# MocKhoaTraiTim.net
KiCad netlist of a schematic drawn in Altium Designer
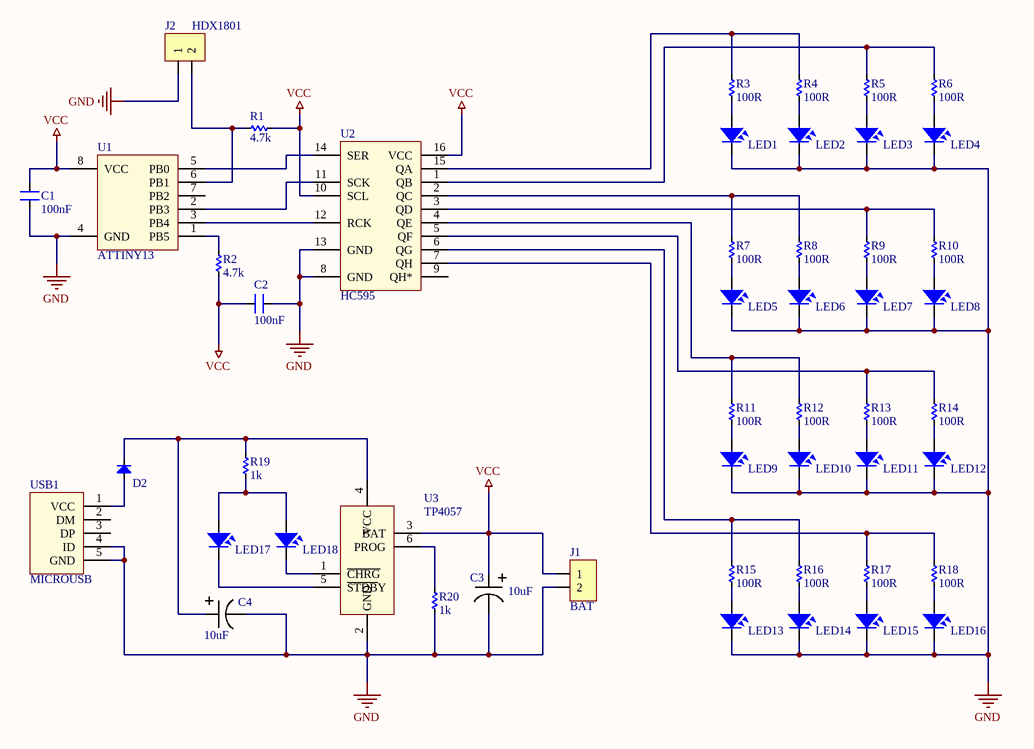
[diagram p0: MocKhoaTraiTim.SchDoc]

(export (version "E")
  (design (tool "Eeschema 10.0.6"))
  (components
    (comp (ref "C1") (value "100nF") (footprint "CN-SMD-0805") (libsource (lib "LIBRARY") (part "CN")))
    (comp (ref "C2") (value "100nF") (footprint "CN-SMD-0805") (libsource (lib "LIBRARY") (part "CN")))
    (comp (ref "C3") (value "10uF") (footprint "CAP1411") (libsource (lib "User") (part "CAP-TANTALUM")))
    (comp (ref "C4") (value "10uF") (footprint "CAP1411") (libsource (lib "") (part "CAP-TANTALUM_1")))
    (comp (ref "D2")
      (value "Diode SMD")
      (footprint "DIO-SMD-123")
      (description "Default Diode")
      (fields (field (name "PUBLISHER") "Altium Limited"))
      (libsource (lib "LIBRARY") (part "Diode SMD"))
    )
    (comp (ref "J1")
      (value "BAT")
      (footprint "JP2-D1T")
      (description "WR-PHD 2.54 mm Angled Socket Header")
      (fields
        (field (name "MANUFACTURER") "Würth Elektronik eiSos GmbH")
        (field (name "PARTNO") "613002143121")
        (field (name "CREATED BY") "Karrer Zheng")
      )
      (libsource (lib "LIBRARY") (part "JP2"))
    )
    (comp (ref "J2")
      (value "HDX1801")
      (footprint "JP2-D1T")
      (description "WR-PHD 2.54 mm Angled Socket Header")
      (fields
        (field (name "MANUFACTURER") "Würth Elektronik eiSos GmbH")
        (field (name "PARTNO") "613002143121")
        (field (name "CREATED BY") "Karrer Zheng")
      )
      (libsource (lib "") (part "JP2_1"))
    )
    (comp (ref "LED1")
      (value "LED")
      (footprint "LED-1206-Yellow")
      (libsource (lib "LIBRARY") (part "LED SMD"))
    )
    (comp (ref "LED2")
      (value "LED")
      (footprint "LED-1206-Yellow")
      (libsource (lib "LIBRARY") (part "LED SMD"))
    )
    (comp (ref "LED3")
      (value "LED")
      (footprint "LED-1206-Yellow")
      (libsource (lib "LIBRARY") (part "LED SMD"))
    )
    (comp (ref "LED4")
      (value "LED")
      (footprint "LED-1206-Yellow")
      (libsource (lib "LIBRARY") (part "LED SMD"))
    )
    (comp (ref "LED5")
      (value "LED")
      (footprint "LED-1206-Yellow")
      (libsource (lib "LIBRARY") (part "LED SMD"))
    )
    (comp (ref "LED6")
      (value "LED")
      (footprint "LED-1206-Yellow")
      (libsource (lib "LIBRARY") (part "LED SMD"))
    )
    (comp (ref "LED7")
      (value "LED")
      (footprint "LED-1206-Yellow")
      (libsource (lib "LIBRARY") (part "LED SMD"))
    )
    (comp (ref "LED8")
      (value "LED")
      (footprint "LED-1206-Yellow")
      (libsource (lib "LIBRARY") (part "LED SMD"))
    )
    (comp (ref "LED9")
      (value "LED")
      (footprint "LED-1206-Yellow")
      (libsource (lib "LIBRARY") (part "LED SMD"))
    )
    (comp (ref "LED10")
      (value "LED")
      (footprint "LED-1206-Yellow")
      (libsource (lib "LIBRARY") (part "LED SMD"))
    )
    (comp (ref "LED11")
      (value "LED")
      (footprint "LED-1206-Yellow")
      (libsource (lib "LIBRARY") (part "LED SMD"))
    )
    (comp (ref "LED12")
      (value "LED")
      (footprint "LED-1206-Yellow")
      (libsource (lib "LIBRARY") (part "LED SMD"))
    )
    (comp (ref "LED13")
      (value "LED")
      (footprint "LED-1206-Yellow")
      (libsource (lib "LIBRARY") (part "LED SMD"))
    )
    (comp (ref "LED14")
      (value "LED")
      (footprint "LED-1206-Yellow")
      (libsource (lib "LIBRARY") (part "LED SMD"))
    )
    (comp (ref "LED15")
      (value "LED")
      (footprint "LED-1206-Yellow")
      (libsource (lib "LIBRARY") (part "LED SMD"))
    )
    (comp (ref "LED16")
      (value "LED")
      (footprint "LED-1206-Yellow")
      (libsource (lib "LIBRARY") (part "LED SMD"))
    )
    (comp (ref "LED17")
      (value "LED")
      (footprint "LED-0805-Yellow")
      (libsource (lib "LIBRARY") (part "LED SMD"))
    )
    (comp (ref "LED18")
      (value "LED")
      (footprint "LED-0805-Yellow")
      (libsource (lib "LIBRARY") (part "LED SMD"))
    )
    (comp (ref "R1")
      (value "4.7k")
      (footprint "RES-SMD-0805")
      (description "Resistor")
      (fields
        (field (name "MANUFACTURER") "Generic Components")
        (field (name "PUBLISHER") "Altium Hobart Technology Centre")
      )
      (libsource (lib "LIBRARY") (part "Res-SMD"))
    )
    (comp (ref "R2")
      (value "4.7k")
      (footprint "RES-SMD-0805")
      (description "Resistor")
      (fields
        (field (name "MANUFACTURER") "Generic Components")
        (field (name "PUBLISHER") "Altium Hobart Technology Centre")
      )
      (libsource (lib "LIBRARY") (part "Res-SMD"))
    )
    (comp (ref "R3")
      (value "100R")
      (footprint "RES-SMD-0805")
      (description "Resistor")
      (fields
        (field (name "MANUFACTURER") "Generic Components")
        (field (name "PUBLISHER") "Altium Hobart Technology Centre")
      )
      (libsource (lib "LIBRARY") (part "Res-SMD"))
    )
    (comp (ref "R4")
      (value "100R")
      (footprint "RES-SMD-0805")
      (description "Resistor")
      (fields
        (field (name "MANUFACTURER") "Generic Components")
        (field (name "PUBLISHER") "Altium Hobart Technology Centre")
      )
      (libsource (lib "LIBRARY") (part "Res-SMD"))
    )
    (comp (ref "R5")
      (value "100R")
      (footprint "RES-SMD-0805")
      (description "Resistor")
      (fields
        (field (name "MANUFACTURER") "Generic Components")
        (field (name "PUBLISHER") "Altium Hobart Technology Centre")
      )
      (libsource (lib "LIBRARY") (part "Res-SMD"))
    )
    (comp (ref "R6")
      (value "100R")
      (footprint "RES-SMD-0805")
      (description "Resistor")
      (fields
        (field (name "MANUFACTURER") "Generic Components")
        (field (name "PUBLISHER") "Altium Hobart Technology Centre")
      )
      (libsource (lib "LIBRARY") (part "Res-SMD"))
    )
    (comp (ref "R7")
      (value "100R")
      (footprint "RES-SMD-0805")
      (description "Resistor")
      (fields
        (field (name "MANUFACTURER") "Generic Components")
        (field (name "PUBLISHER") "Altium Hobart Technology Centre")
      )
      (libsource (lib "LIBRARY") (part "Res-SMD"))
    )
    (comp (ref "R8")
      (value "100R")
      (footprint "RES-SMD-0805")
      (description "Resistor")
      (fields
        (field (name "MANUFACTURER") "Generic Components")
        (field (name "PUBLISHER") "Altium Hobart Technology Centre")
      )
      (libsource (lib "LIBRARY") (part "Res-SMD"))
    )
    (comp (ref "R9")
      (value "100R")
      (footprint "RES-SMD-0805")
      (description "Resistor")
      (fields
        (field (name "MANUFACTURER") "Generic Components")
        (field (name "PUBLISHER") "Altium Hobart Technology Centre")
      )
      (libsource (lib "LIBRARY") (part "Res-SMD"))
    )
    (comp (ref "R10")
      (value "100R")
      (footprint "RES-SMD-0805")
      (description "Resistor")
      (fields
        (field (name "MANUFACTURER") "Generic Components")
        (field (name "PUBLISHER") "Altium Hobart Technology Centre")
      )
      (libsource (lib "LIBRARY") (part "Res-SMD"))
    )
    (comp (ref "R11")
      (value "100R")
      (footprint "RES-SMD-0805")
      (description "Resistor")
      (fields
        (field (name "MANUFACTURER") "Generic Components")
        (field (name "PUBLISHER") "Altium Hobart Technology Centre")
      )
      (libsource (lib "LIBRARY") (part "Res-SMD"))
    )
    (comp (ref "R12")
      (value "100R")
      (footprint "RES-SMD-0805")
      (description "Resistor")
      (fields
        (field (name "MANUFACTURER") "Generic Components")
        (field (name "PUBLISHER") "Altium Hobart Technology Centre")
      )
      (libsource (lib "LIBRARY") (part "Res-SMD"))
    )
    (comp (ref "R13")
      (value "100R")
      (footprint "RES-SMD-0805")
      (description "Resistor")
      (fields
        (field (name "MANUFACTURER") "Generic Components")
        (field (name "PUBLISHER") "Altium Hobart Technology Centre")
      )
      (libsource (lib "LIBRARY") (part "Res-SMD"))
    )
    (comp (ref "R14")
      (value "100R")
      (footprint "RES-SMD-0805")
      (description "Resistor")
      (fields
        (field (name "MANUFACTURER") "Generic Components")
        (field (name "PUBLISHER") "Altium Hobart Technology Centre")
      )
      (libsource (lib "LIBRARY") (part "Res-SMD"))
    )
    (comp (ref "R15")
      (value "100R")
      (footprint "RES-SMD-0805")
      (description "Resistor")
      (fields
        (field (name "MANUFACTURER") "Generic Components")
        (field (name "PUBLISHER") "Altium Hobart Technology Centre")
      )
      (libsource (lib "LIBRARY") (part "Res-SMD"))
    )
    (comp (ref "R16")
      (value "100R")
      (footprint "RES-SMD-0805")
      (description "Resistor")
      (fields
        (field (name "MANUFACTURER") "Generic Components")
        (field (name "PUBLISHER") "Altium Hobart Technology Centre")
      )
      (libsource (lib "LIBRARY") (part "Res-SMD"))
    )
    (comp (ref "R17")
      (value "100R")
      (footprint "RES-SMD-0805")
      (description "Resistor")
      (fields
        (field (name "MANUFACTURER") "Generic Components")
        (field (name "PUBLISHER") "Altium Hobart Technology Centre")
      )
      (libsource (lib "LIBRARY") (part "Res-SMD"))
    )
    (comp (ref "R18")
      (value "100R")
      (footprint "RES-SMD-0805")
      (description "Resistor")
      (fields
        (field (name "MANUFACTURER") "Generic Components")
        (field (name "PUBLISHER") "Altium Hobart Technology Centre")
      )
      (libsource (lib "LIBRARY") (part "Res-SMD"))
    )
    (comp (ref "R19")
      (value "1k")
      (footprint "RES-SMD-0805")
      (description "Resistor")
      (fields
        (field (name "MANUFACTURER") "Generic Components")
        (field (name "PUBLISHER") "Altium Hobart Technology Centre")
      )
      (libsource (lib "LIBRARY") (part "Res-SMD"))
    )
    (comp (ref "R20")
      (value "1k")
      (footprint "RES-SMD-0805")
      (description "Resistor")
      (fields
        (field (name "MANUFACTURER") "Generic Components")
        (field (name "PUBLISHER") "Altium Hobart Technology Centre")
      )
      (libsource (lib "LIBRARY") (part "Res-SMD"))
    )
    (comp (ref "U1") (value "ATTINY13") (footprint "TINY13") (libsource (lib "User") (part "TINY13")))
    (comp (ref "U2") (value "HC595") (footprint "SOP16") (libsource (lib "User") (part "HC595")))
    (comp (ref "U3") (value "TP4057") (footprint "SOT23-6") (libsource (lib "User") (part "TP4057")))
    (comp (ref "USB1") (value "MICROUSB") (footprint "MICROUSB") (libsource (lib "User") (part "MICROUSB")))
  )
  (nets
    (net (code "1") (name "GND") (class "Default")
      (node (ref "C1") (pin "1") (pinfunction "1_1") (pintype "passive"))
      (node (ref "C2") (pin "1") (pinfunction "1_1") (pintype "passive"))
      (node (ref "C3") (pin "2") (pinfunction "2_2") (pintype "passive"))
      (node (ref "C4") (pin "2") (pinfunction "2_2") (pintype "passive"))
      (node (ref "J1") (pin "2") (pinfunction "2_2") (pintype "passive"))
      (node (ref "J2") (pin "1") (pinfunction "1_1") (pintype "passive"))
      (node (ref "LED1") (pin "2") (pinfunction "2_2") (pintype "passive"))
      (node (ref "LED10") (pin "2") (pinfunction "2_2") (pintype "passive"))
      (node (ref "LED11") (pin "2") (pinfunction "2_2") (pintype "passive"))
      (node (ref "LED12") (pin "2") (pinfunction "2_2") (pintype "passive"))
      (node (ref "LED13") (pin "2") (pinfunction "2_2") (pintype "passive"))
      (node (ref "LED14") (pin "2") (pinfunction "2_2") (pintype "passive"))
      (node (ref "LED15") (pin "2") (pinfunction "2_2") (pintype "passive"))
      (node (ref "LED16") (pin "2") (pinfunction "2_2") (pintype "passive"))
      (node (ref "LED2") (pin "2") (pinfunction "2_2") (pintype "passive"))
      (node (ref "LED3") (pin "2") (pinfunction "2_2") (pintype "passive"))
      (node (ref "LED4") (pin "2") (pinfunction "2_2") (pintype "passive"))
      (node (ref "LED5") (pin "2") (pinfunction "2_2") (pintype "passive"))
      (node (ref "LED6") (pin "2") (pinfunction "2_2") (pintype "passive"))
      (node (ref "LED7") (pin "2") (pinfunction "2_2") (pintype "passive"))
      (node (ref "LED8") (pin "2") (pinfunction "2_2") (pintype "passive"))
      (node (ref "LED9") (pin "2") (pinfunction "2_2") (pintype "passive"))
      (node (ref "R20") (pin "1") (pinfunction "1_1") (pintype "passive"))
      (node (ref "U1") (pin "4") (pinfunction "GND_4") (pintype "passive"))
      (node (ref "U2") (pin "13") (pinfunction "GND_13") (pintype "passive"))
      (node (ref "U2") (pin "8") (pinfunction "GND_8") (pintype "passive"))
      (node (ref "U3") (pin "2") (pinfunction "GND_2") (pintype "passive"))
      (node (ref "USB1") (pin "4") (pinfunction "ID_4") (pintype "passive"))
      (node (ref "USB1") (pin "5") (pinfunction "GND_5") (pintype "passive"))
    )
    (net (code "2") (name "Net-(D2-A)") (class "Default")
      (node (ref "D2") (pin "1") (pinfunction "A_1") (pintype "passive"))
      (node (ref "USB1") (pin "1") (pinfunction "VCC_1") (pintype "passive"))
    )
    (net (code "3") (name "Net-(D2-K)") (class "Default")
      (node (ref "C4") (pin "1") (pinfunction "1_1") (pintype "passive"))
      (node (ref "D2") (pin "2") (pinfunction "K_2") (pintype "passive"))
      (node (ref "R19") (pin "2") (pinfunction "2_2") (pintype "passive"))
      (node (ref "U3") (pin "4") (pinfunction "VCC_4") (pintype "passive"))
    )
    (net (code "4") (name "Net-(LED1-Pad1)") (class "Default")
      (node (ref "LED1") (pin "1") (pinfunction "1_1") (pintype "passive"))
      (node (ref "R3") (pin "1") (pinfunction "1_1") (pintype "passive"))
    )
    (net (code "5") (name "Net-(LED2-Pad1)") (class "Default")
      (node (ref "LED2") (pin "1") (pinfunction "1_1") (pintype "passive"))
      (node (ref "R4") (pin "1") (pinfunction "1_1") (pintype "passive"))
    )
    (net (code "6") (name "Net-(LED3-Pad1)") (class "Default")
      (node (ref "LED3") (pin "1") (pinfunction "1_1") (pintype "passive"))
      (node (ref "R5") (pin "1") (pinfunction "1_1") (pintype "passive"))
    )
    (net (code "7") (name "Net-(LED4-Pad1)") (class "Default")
      (node (ref "LED4") (pin "1") (pinfunction "1_1") (pintype "passive"))
      (node (ref "R6") (pin "1") (pinfunction "1_1") (pintype "passive"))
    )
    (net (code "8") (name "Net-(LED5-Pad1)") (class "Default")
      (node (ref "LED5") (pin "1") (pinfunction "1_1") (pintype "passive"))
      (node (ref "R7") (pin "1") (pinfunction "1_1") (pintype "passive"))
    )
    (net (code "9") (name "Net-(LED6-Pad1)") (class "Default")
      (node (ref "LED6") (pin "1") (pinfunction "1_1") (pintype "passive"))
      (node (ref "R8") (pin "1") (pinfunction "1_1") (pintype "passive"))
    )
    (net (code "10") (name "Net-(LED7-Pad1)") (class "Default")
      (node (ref "LED7") (pin "1") (pinfunction "1_1") (pintype "passive"))
      (node (ref "R9") (pin "1") (pinfunction "1_1") (pintype "passive"))
    )
    (net (code "11") (name "Net-(LED8-Pad1)") (class "Default")
      (node (ref "LED8") (pin "1") (pinfunction "1_1") (pintype "passive"))
      (node (ref "R10") (pin "1") (pinfunction "1_1") (pintype "passive"))
    )
    (net (code "12") (name "Net-(LED9-Pad1)") (class "Default")
      (node (ref "LED9") (pin "1") (pinfunction "1_1") (pintype "passive"))
      (node (ref "R11") (pin "1") (pinfunction "1_1") (pintype "passive"))
    )
    (net (code "13") (name "Net-(LED10-Pad1)") (class "Default")
      (node (ref "LED10") (pin "1") (pinfunction "1_1") (pintype "passive"))
      (node (ref "R12") (pin "1") (pinfunction "1_1") (pintype "passive"))
    )
    (net (code "14") (name "Net-(LED11-Pad1)") (class "Default")
      (node (ref "LED11") (pin "1") (pinfunction "1_1") (pintype "passive"))
      (node (ref "R13") (pin "1") (pinfunction "1_1") (pintype "passive"))
    )
    (net (code "15") (name "Net-(LED12-Pad1)") (class "Default")
      (node (ref "LED12") (pin "1") (pinfunction "1_1") (pintype "passive"))
      (node (ref "R14") (pin "1") (pinfunction "1_1") (pintype "passive"))
    )
    (net (code "16") (name "Net-(LED13-Pad1)") (class "Default")
      (node (ref "LED13") (pin "1") (pinfunction "1_1") (pintype "passive"))
      (node (ref "R15") (pin "1") (pinfunction "1_1") (pintype "passive"))
    )
    (net (code "17") (name "Net-(LED14-Pad1)") (class "Default")
      (node (ref "LED14") (pin "1") (pinfunction "1_1") (pintype "passive"))
      (node (ref "R16") (pin "1") (pinfunction "1_1") (pintype "passive"))
    )
    (net (code "18") (name "Net-(LED15-Pad1)") (class "Default")
      (node (ref "LED15") (pin "1") (pinfunction "1_1") (pintype "passive"))
      (node (ref "R17") (pin "1") (pinfunction "1_1") (pintype "passive"))
    )
    (net (code "19") (name "Net-(LED16-Pad1)") (class "Default")
      (node (ref "LED16") (pin "1") (pinfunction "1_1") (pintype "passive"))
      (node (ref "R18") (pin "1") (pinfunction "1_1") (pintype "passive"))
    )
    (net (code "20") (name "Net-(LED17-Pad1)") (class "Default")
      (node (ref "LED17") (pin "1") (pinfunction "1_1") (pintype "passive"))
      (node (ref "LED18") (pin "1") (pinfunction "1_1") (pintype "passive"))
      (node (ref "R19") (pin "1") (pinfunction "1_1") (pintype "passive"))
    )
    (net (code "21") (name "Net-(U1-PB0)") (class "Default")
      (node (ref "U1") (pin "5") (pinfunction "PB0_5") (pintype "passive"))
      (node (ref "U2") (pin "14") (pinfunction "SER_14") (pintype "passive"))
    )
    (net (code "22") (name "Net-(U1-PB1)") (class "Default")
      (node (ref "J2") (pin "2") (pinfunction "2_2") (pintype "passive"))
      (node (ref "R1") (pin "1") (pinfunction "1_1") (pintype "passive"))
      (node (ref "U1") (pin "6") (pinfunction "PB1_6") (pintype "passive"))
    )
    (net (code "23") (name "Net-(U1-PB3)") (class "Default")
      (node (ref "U1") (pin "2") (pinfunction "PB3_2") (pintype "passive"))
      (node (ref "U2") (pin "11") (pinfunction "SCK_11") (pintype "passive"))
    )
    (net (code "24") (name "Net-(U1-PB4)") (class "Default")
      (node (ref "U1") (pin "3") (pinfunction "PB4_3") (pintype "passive"))
      (node (ref "U2") (pin "12") (pinfunction "RCK_12") (pintype "passive"))
    )
    (net (code "25") (name "Net-(U1-PB5)") (class "Default")
      (node (ref "R2") (pin "1") (pinfunction "1_1") (pintype "passive"))
      (node (ref "U1") (pin "1") (pinfunction "PB5_1") (pintype "passive"))
    )
    (net (code "26") (name "Net-(U2-QA)") (class "Default")
      (node (ref "R3") (pin "2") (pinfunction "2_2") (pintype "passive"))
      (node (ref "R4") (pin "2") (pinfunction "2_2") (pintype "passive"))
      (node (ref "U2") (pin "15") (pinfunction "QA_15") (pintype "passive"))
    )
    (net (code "27") (name "Net-(U2-QB)") (class "Default")
      (node (ref "R5") (pin "2") (pinfunction "2_2") (pintype "passive"))
      (node (ref "R6") (pin "2") (pinfunction "2_2") (pintype "passive"))
      (node (ref "U2") (pin "1") (pinfunction "QB_1") (pintype "passive"))
    )
    (net (code "28") (name "Net-(U2-QC)") (class "Default")
      (node (ref "R7") (pin "2") (pinfunction "2_2") (pintype "passive"))
      (node (ref "R8") (pin "2") (pinfunction "2_2") (pintype "passive"))
      (node (ref "U2") (pin "2") (pinfunction "QC_2") (pintype "passive"))
    )
    (net (code "29") (name "Net-(U2-QD)") (class "Default")
      (node (ref "R10") (pin "2") (pinfunction "2_2") (pintype "passive"))
      (node (ref "R9") (pin "2") (pinfunction "2_2") (pintype "passive"))
      (node (ref "U2") (pin "3") (pinfunction "QD_3") (pintype "passive"))
    )
    (net (code "30") (name "Net-(U2-QE)") (class "Default")
      (node (ref "R11") (pin "2") (pinfunction "2_2") (pintype "passive"))
      (node (ref "R12") (pin "2") (pinfunction "2_2") (pintype "passive"))
      (node (ref "U2") (pin "4") (pinfunction "QE_4") (pintype "passive"))
    )
    (net (code "31") (name "Net-(U2-QF)") (class "Default")
      (node (ref "R13") (pin "2") (pinfunction "2_2") (pintype "passive"))
      (node (ref "R14") (pin "2") (pinfunction "2_2") (pintype "passive"))
      (node (ref "U2") (pin "5") (pinfunction "QF_5") (pintype "passive"))
    )
    (net (code "32") (name "Net-(U2-QG)") (class "Default")
      (node (ref "R15") (pin "2") (pinfunction "2_2") (pintype "passive"))
      (node (ref "R16") (pin "2") (pinfunction "2_2") (pintype "passive"))
      (node (ref "U2") (pin "6") (pinfunction "QG_6") (pintype "passive"))
    )
    (net (code "33") (name "Net-(U2-QH)") (class "Default")
      (node (ref "R17") (pin "2") (pinfunction "2_2") (pintype "passive"))
      (node (ref "R18") (pin "2") (pinfunction "2_2") (pintype "passive"))
      (node (ref "U2") (pin "7") (pinfunction "QH_7") (pintype "passive"))
    )
    (net (code "34") (name "Net-(U3-PROG)") (class "Default")
      (node (ref "R20") (pin "2") (pinfunction "2_2") (pintype "passive"))
      (node (ref "U3") (pin "6") (pinfunction "PROG_6") (pintype "passive"))
    )
    (net (code "35") (name "Net-(U3-~{CHRG})") (class "Default")
      (node (ref "LED18") (pin "2") (pinfunction "2_2") (pintype "passive"))
      (node (ref "U3") (pin "1") (pinfunction "~{CHRG}_1") (pintype "passive"))
    )
    (net (code "36") (name "Net-(U3-~{STDB}Y)") (class "Default")
      (node (ref "LED17") (pin "2") (pinfunction "2_2") (pintype "passive"))
      (node (ref "U3") (pin "5") (pinfunction "~{STDB}Y_5") (pintype "passive"))
    )
    (net (code "37") (name "VCC") (class "Default")
      (node (ref "C1") (pin "2") (pinfunction "2_2") (pintype "passive"))
      (node (ref "C2") (pin "2") (pinfunction "2_2") (pintype "passive"))
      (node (ref "C3") (pin "1") (pinfunction "1_1") (pintype "passive"))
      (node (ref "J1") (pin "1") (pinfunction "1_1") (pintype "passive"))
      (node (ref "R1") (pin "2") (pinfunction "2_2") (pintype "passive"))
      (node (ref "R2") (pin "2") (pinfunction "2_2") (pintype "passive"))
      (node (ref "U1") (pin "8") (pinfunction "VCC_8") (pintype "passive"))
      (node (ref "U2") (pin "10") (pinfunction "SCL_10") (pintype "passive"))
      (node (ref "U2") (pin "16") (pinfunction "VCC_16") (pintype "passive"))
      (node (ref "U3") (pin "3") (pinfunction "BAT_3") (pintype "passive"))
    )
    (net (code "38") (name "unconnected-(U1-PB2-Pad7)") (class "Default")
      (node (ref "U1") (pin "7") (pinfunction "PB2_7") (pintype "passive"))
    )
    (net (code "39") (name "unconnected-(U2-QH*-Pad9)") (class "Default")
      (node (ref "U2") (pin "9") (pinfunction "QH*_9") (pintype "passive"))
    )
    (net (code "40") (name "unconnected-(USB1-DM-Pad2)") (class "Default")
      (node (ref "USB1") (pin "2") (pinfunction "DM_2") (pintype "passive"))
    )
    (net (code "41") (name "unconnected-(USB1-DP-Pad3)") (class "Default")
      (node (ref "USB1") (pin "3") (pinfunction "DP_3") (pintype "passive"))
    )
  )
)
